# OptoIso_H2L.net
KiCad netlist of a schematic drawn in Altium Designer
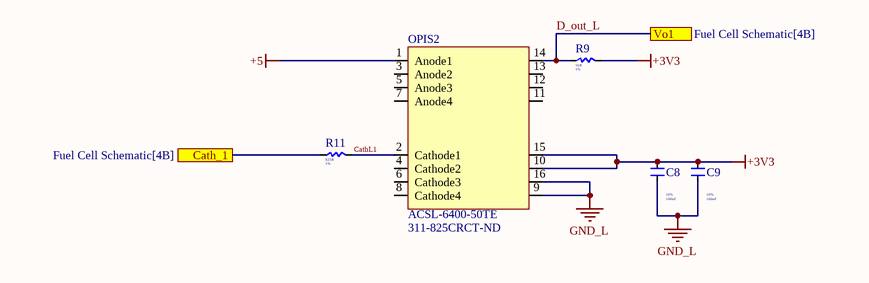
[diagram p0: OptoIso_H2L.SchDoc]

(export (version "E")
  (design (tool "Eeschema 10.0.6"))
  (components
    (comp (ref "C8")
      (value "~")
      (footprint "Capacitor_Kemet_0805")
      (description "Cap Ceramic 0.1uF 35V X7R 10% SMD 0805 125°C Paper T/R")
      (fields
        (field (name "MANUFACTURER") "KEMET")
        (field (name "MANUFACTURER PART NUMBER") "C0805C104K6RACTU")
        (field (name "TOLERANCE") "10%")
        (field (name "CAPACITANCE") "100nF")
      )
      (libsource (lib "Schlib1") (part "C0805C104K6RACTU"))
    )
    (comp (ref "C9")
      (value "~")
      (footprint "Capacitor_Kemet_0805")
      (description "Cap Ceramic 0.1uF 35V X7R 10% SMD 0805 125°C Paper T/R")
      (fields
        (field (name "MANUFACTURER") "KEMET")
        (field (name "MANUFACTURER PART NUMBER") "C0805C104K6RACTU")
        (field (name "TOLERANCE") "10%")
        (field (name "CAPACITANCE") "100nF")
      )
      (libsource (lib "Schlib1") (part "C0805C104K6RACTU"))
    )
    (comp (ref "OPIS2")
      (value "~")
      (footprint "Opto_Isolator_ACSL6400_50TE")
      (description "OPTOISO 2.5KV 4CH OPEN COLL 16SO")
      (fields
        (field (name "MANUFACTURER") "Broadcom Avago")
        (field (name "MANUFACTURER PART NUMBER") "ACSL-6400-50TE")
        (field (name "SUPPLIER PART NUMBER 2") "311-825CRCT-ND")
      )
      (libsource (lib "Schlib1") (part "ACSL-6400-50TE"))
    )
    (comp (ref "R9")
      (value "~")
      (footprint "Resistor_YAGEO_0805")
      (description "Res Thick Film 0805 1K Ohm 1% 0.125W(1/8W) ±100ppm/C Pad SMD T/R")
      (fields
        (field (name "MANUFACTURER") "Yageo")
        (field (name "MANUFACTURER PART NUMBER") "RC0805FR-071KP")
        (field (name "RESISTANCE") "1kR")
        (field (name "TOLERANCE") "1%")
      )
      (libsource (lib "Schlib1") (part "RC0805FR-071KP"))
    )
    (comp (ref "R11")
      (value "~")
      (footprint "Resistor_YAGEO_0805")
      (description "825 Ohms ±1% 0.125W, 1/8W Chip Resistor 0805 (2012 Metric) Moisture Resistant Thick Film")
      (fields
        (field (name "MANUFACTURER") "Yageo")
        (field (name "MANUFACTURER PART NUMBER") "RC0805FR-07825RL")
        (field (name "RESISTANCE") "825R")
        (field (name "TOLERANCE") "1%")
      )
      (libsource (lib "Schlib1") (part "RC0805FR-07825RL"))
    )
  )
  (nets
    (net (code "1") (name "+3V3") (class "Default")
      (node (ref "C8") (pin "2") (pinfunction "2_2") (pintype "passive"))
      (node (ref "C9") (pin "2") (pinfunction "2_2") (pintype "passive"))
      (node (ref "OPIS2") (pin "10") (pinfunction "VDD_10") (pintype "passive"))
      (node (ref "OPIS2") (pin "15") (pinfunction "VDD_15") (pintype "passive"))
      (node (ref "R9") (pin "2") (pinfunction "2_2") (pintype "passive"))
    )
    (net (code "2") (name "+5") (class "Default")
      (node (ref "OPIS2") (pin "1") (pinfunction "Anode1_1") (pintype "passive"))
    )
    (net (code "3") (name "/CathL1") (class "Default")
      (node (ref "OPIS2") (pin "2") (pinfunction "Cathode1_2") (pintype "passive"))
      (node (ref "R11") (pin "2") (pinfunction "2_2") (pintype "passive"))
    )
    (net (code "4") (name "/Cath_1") (class "Default")
      (node (ref "R11") (pin "1") (pinfunction "1_1") (pintype "passive"))
    )
    (net (code "5") (name "/D_out_L") (class "Default")
      (node (ref "OPIS2") (pin "14") (pinfunction "Vo1_14") (pintype "passive"))
      (node (ref "R9") (pin "1") (pinfunction "1_1") (pintype "passive"))
    )
    (net (code "6") (name "GND_L") (class "Default")
      (node (ref "C8") (pin "1") (pinfunction "1_1") (pintype "passive"))
      (node (ref "C9") (pin "1") (pinfunction "1_1") (pintype "passive"))
      (node (ref "OPIS2") (pin "16") (pinfunction "Ground_16") (pintype "passive"))
      (node (ref "OPIS2") (pin "9") (pinfunction "Ground_9") (pintype "passive"))
    )
    (net (code "7") (name "unconnected-(OPIS2-Anode2-Pad3)") (class "Default")
      (node (ref "OPIS2") (pin "3") (pinfunction "Anode2_3") (pintype "passive"))
    )
    (net (code "8") (name "unconnected-(OPIS2-Anode3-Pad5)") (class "Default")
      (node (ref "OPIS2") (pin "5") (pinfunction "Anode3_5") (pintype "passive"))
    )
    (net (code "9") (name "unconnected-(OPIS2-Anode4-Pad7)") (class "Default")
      (node (ref "OPIS2") (pin "7") (pinfunction "Anode4_7") (pintype "passive"))
    )
    (net (code "10") (name "unconnected-(OPIS2-Cathode2-Pad4)") (class "Default")
      (node (ref "OPIS2") (pin "4") (pinfunction "Cathode2_4") (pintype "passive"))
    )
    (net (code "11") (name "unconnected-(OPIS2-Cathode3-Pad6)") (class "Default")
      (node (ref "OPIS2") (pin "6") (pinfunction "Cathode3_6") (pintype "passive"))
    )
    (net (code "12") (name "unconnected-(OPIS2-Cathode4-Pad8)") (class "Default")
      (node (ref "OPIS2") (pin "8") (pinfunction "Cathode4_8") (pintype "passive"))
    )
    (net (code "13") (name "unconnected-(OPIS2-Vo2-Pad13)") (class "Default")
      (node (ref "OPIS2") (pin "13") (pinfunction "Vo2_13") (pintype "passive"))
    )
    (net (code "14") (name "unconnected-(OPIS2-Vo3-Pad12)") (class "Default")
      (node (ref "OPIS2") (pin "12") (pinfunction "Vo3_12") (pintype "passive"))
    )
    (net (code "15") (name "unconnected-(OPIS2-Vo4-Pad11)") (class "Default")
      (node (ref "OPIS2") (pin "11") (pinfunction "Vo4_11") (pintype "passive"))
    )
  )
)
